# W5500_Module.net
KiCad netlist of a schematic drawn in Altium Designer
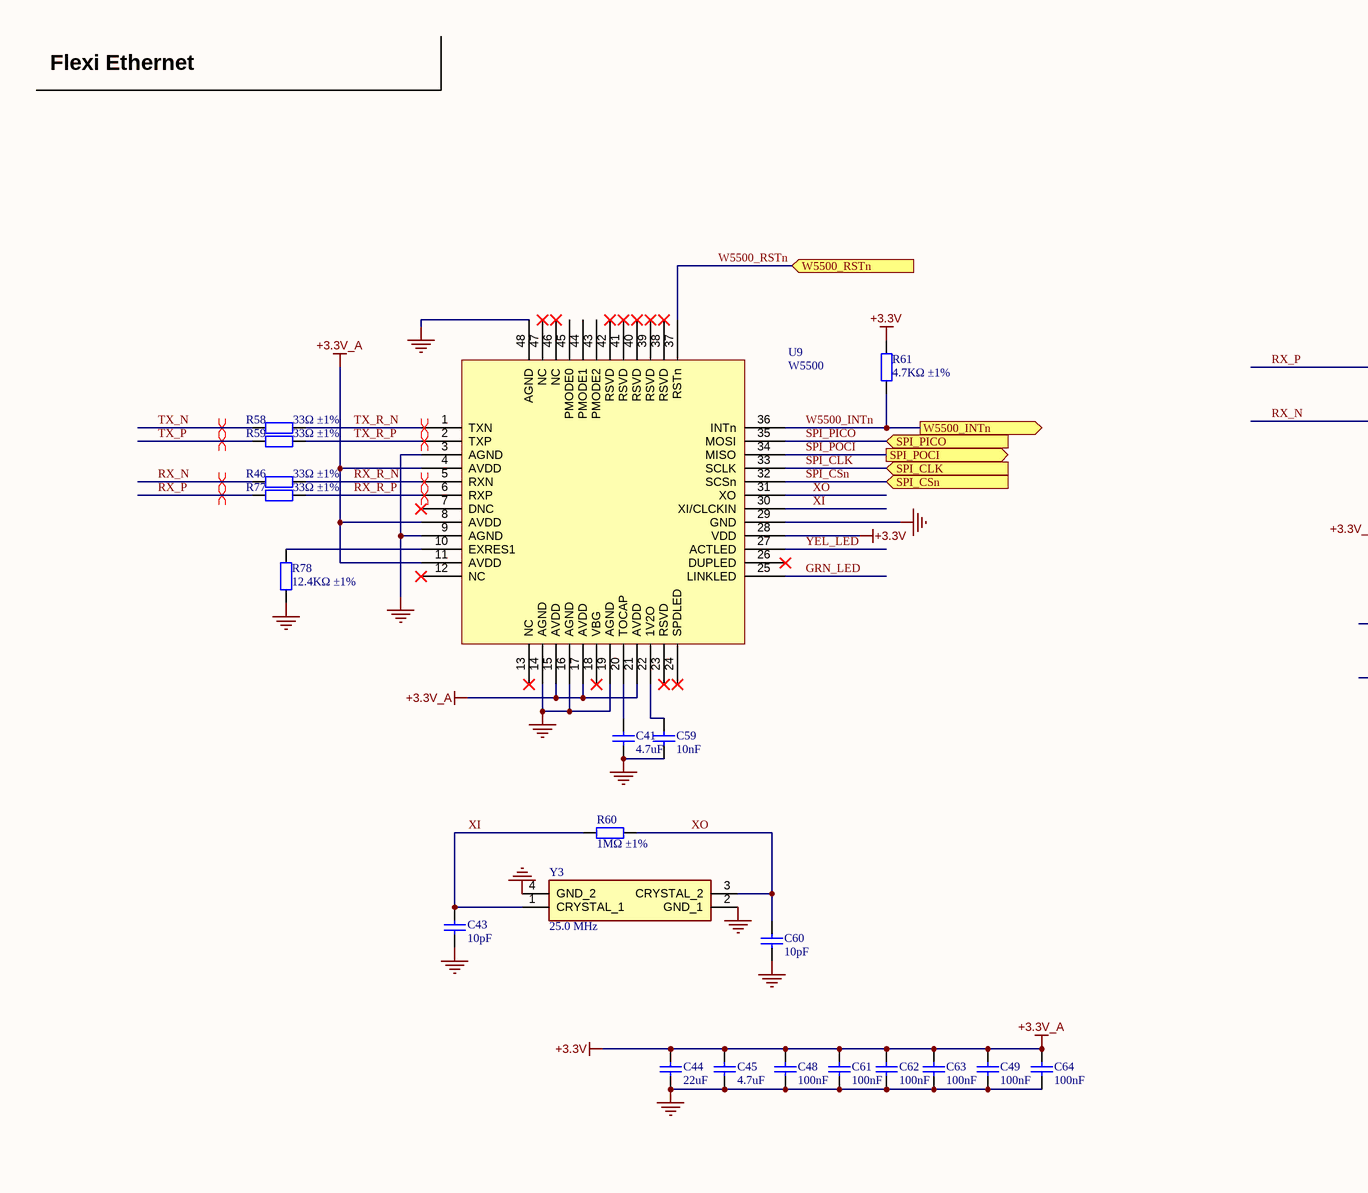
[diagram p0: W5500_Module.SchDoc, left]
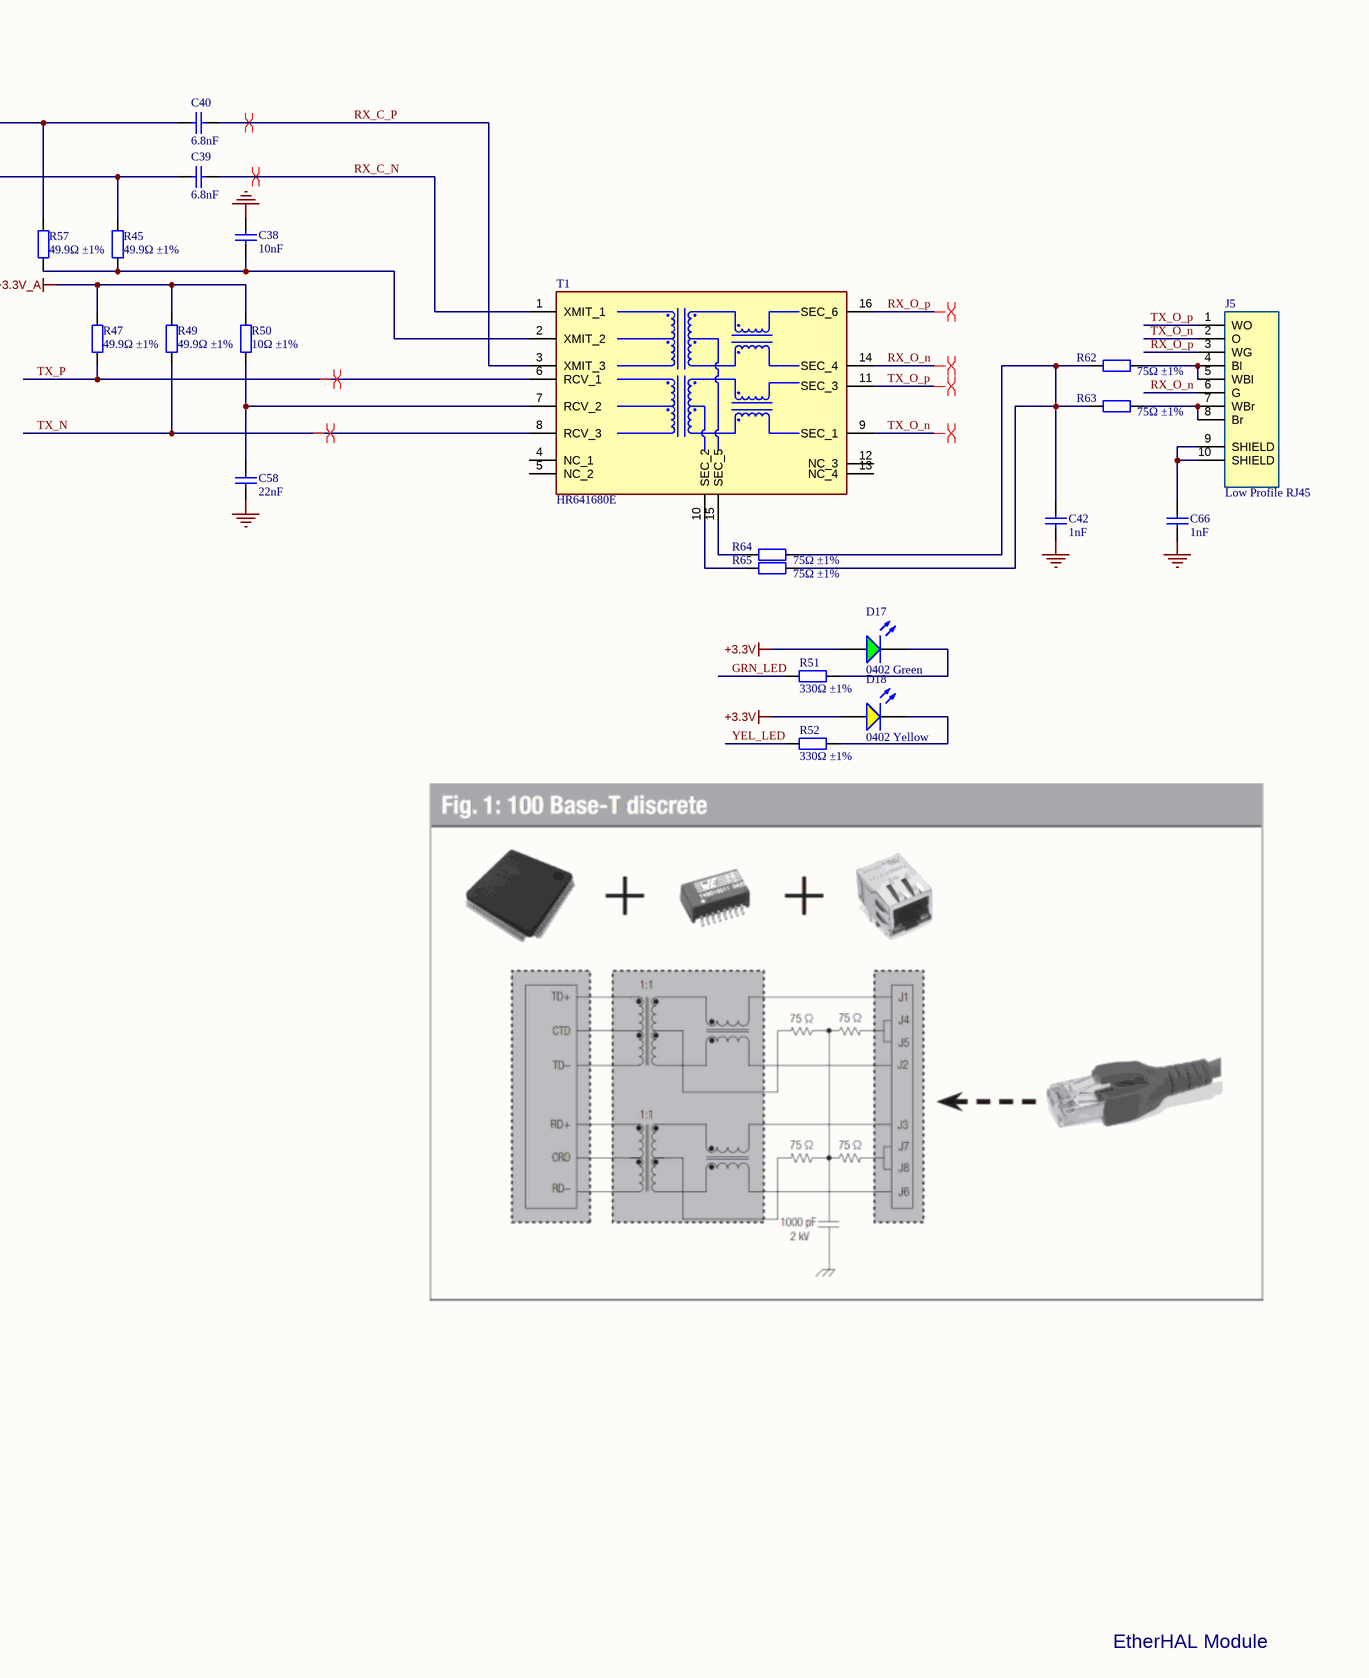
[diagram p1: W5500_Module.SchDoc, right]

(export (version "E")
  (design (tool "Eeschema 10.0.6"))
  (components
    (comp (ref "C38")
      (value "10nF")
      (footprint "0402_C")
      (description "Chip capacitors")
      (fields
        (field (name "MANUFACTURER") "Samsung Electro-Mechanics")
        (field (name "PARTNUMBER") "CL05B103KB5NNNC")
      )
      (libsource (lib "Cap") (part "0402 10nF (103) 10% 50V"))
    )
    (comp (ref "C39")
      (value "6.8nF")
      (footprint "0402_C")
      (description "Chip capacitors")
      (fields
        (field (name "MANUFACTURER") "Guangdong Fenghua Advanced Tech")
        (field (name "PARTNUMBER") "0402B682K500NT")
      )
      (libsource (lib "Cap") (part "0402 6.8nF (682) 10% 50V"))
    )
    (comp (ref "C40")
      (value "6.8nF")
      (footprint "0402_C")
      (description "Chip capacitors")
      (fields
        (field (name "MANUFACTURER") "Guangdong Fenghua Advanced Tech")
        (field (name "PARTNUMBER") "0402B682K500NT")
      )
      (libsource (lib "Cap") (part "0402 6.8nF (682) 10% 50V"))
    )
    (comp (ref "C41")
      (value "4.7uF")
      (footprint "0402_C")
      (description "Chip capacitor")
      (fields
        (field (name "MANUFACTURER") "Samsung Electro-Mechanics")
        (field (name "PARTNUMBER") "CL05A475MP5NRNC")
      )
      (libsource (lib "Cap") (part "0402 4.7uF (475) 20% 10V"))
    )
    (comp (ref "C42")
      (value "1nF")
      (footprint "1206_C")
      (description "Chip capacitors")
      (fields
        (field (name "MANUFACTURER") "Samsung Electro-Mechanics")
        (field (name "PARTNUMBER") "CL31B102KGFNNNE")
      )
      (libsource (lib "Cap") (part "1206 1nF (102) 10% 500V"))
    )
    (comp (ref "C43")
      (value "10pF")
      (footprint "0402_C")
      (description "Chip capacitors")
      (fields
        (field (name "MANUFACTURER") "Samsung Electro-Mechanics")
        (field (name "PARTNUMBER") "CL05C100JB5NNNC")
      )
      (libsource (lib "Cap") (part "0402 10pF (100) 5% 50V"))
    )
    (comp (ref "C44")
      (value "22uF")
      (footprint "0805_C")
      (description "Chip capacitors")
      (fields
        (field (name "MANUFACTURER") "Samsung Electro-Mechanics")
        (field (name "PARTNUMBER") "CL21A226MAQNNNE")
      )
      (libsource (lib "Cap") (part "0805 22uF (226) 20% 25V"))
    )
    (comp (ref "C45")
      (value "4.7uF")
      (footprint "0603_C")
      (description "Chip capacitors")
      (fields
        (field (name "MANUFACTURER") "Samsung Electro-Mechanics")
        (field (name "PARTNUMBER") "CL10A475KO8NNNC")
      )
      (libsource (lib "Cap") (part "0603 4.7uF (475) 10% 16V"))
    )
    (comp (ref "C48")
      (value "100nF")
      (footprint "0402_C")
      (description "Chip capacitors")
      (fields
        (field (name "MANUFACTURER") "Samsung Electro-Mechanics")
        (field (name "PARTNUMBER") "CL05B104KO5NNNC")
      )
      (libsource (lib "Cap") (part "0402 100nF (104) 10% 16V"))
    )
    (comp (ref "C49")
      (value "100nF")
      (footprint "0402_C")
      (description "Chip capacitors")
      (fields
        (field (name "MANUFACTURER") "Samsung Electro-Mechanics")
        (field (name "PARTNUMBER") "CL05B104KO5NNNC")
      )
      (libsource (lib "Cap") (part "0402 100nF (104) 10% 16V"))
    )
    (comp (ref "C58")
      (value "22nF")
      (footprint "0402_C")
      (description "Chip capacitors")
      (fields
        (field (name "MANUFACTURER") "Guangdong Fenghua Advanced Tech")
        (field (name "PARTNUMBER") "0402B223K500NT")
      )
      (libsource (lib "Cap") (part "0402 22nF (223) 10% 50V"))
    )
    (comp (ref "C59")
      (value "10nF")
      (footprint "0402_C")
      (description "Chip capacitors")
      (fields
        (field (name "MANUFACTURER") "Samsung Electro-Mechanics")
        (field (name "PARTNUMBER") "CL05B103KB5NNNC")
      )
      (libsource (lib "Cap") (part "0402 10nF (103) 10% 50V"))
    )
    (comp (ref "C60")
      (value "10pF")
      (footprint "0402_C")
      (description "Chip capacitors")
      (fields
        (field (name "MANUFACTURER") "Samsung Electro-Mechanics")
        (field (name "PARTNUMBER") "CL05C100JB5NNNC")
      )
      (libsource (lib "Cap") (part "0402 10pF (100) 5% 50V"))
    )
    (comp (ref "C61")
      (value "100nF")
      (footprint "0402_C")
      (description "Chip capacitors")
      (fields
        (field (name "MANUFACTURER") "Samsung Electro-Mechanics")
        (field (name "PARTNUMBER") "CL05B104KO5NNNC")
      )
      (libsource (lib "Cap") (part "0402 100nF (104) 10% 16V"))
    )
    (comp (ref "C62")
      (value "100nF")
      (footprint "0402_C")
      (description "Chip capacitors")
      (fields
        (field (name "MANUFACTURER") "Samsung Electro-Mechanics")
        (field (name "PARTNUMBER") "CL05B104KO5NNNC")
      )
      (libsource (lib "Cap") (part "0402 100nF (104) 10% 16V"))
    )
    (comp (ref "C63")
      (value "100nF")
      (footprint "0402_C")
      (description "Chip capacitors")
      (fields
        (field (name "MANUFACTURER") "Samsung Electro-Mechanics")
        (field (name "PARTNUMBER") "CL05B104KO5NNNC")
      )
      (libsource (lib "Cap") (part "0402 100nF (104) 10% 16V"))
    )
    (comp (ref "C64")
      (value "100nF")
      (footprint "0402_C")
      (description "Chip capacitors")
      (fields
        (field (name "MANUFACTURER") "Samsung Electro-Mechanics")
        (field (name "PARTNUMBER") "CL05B104KO5NNNC")
      )
      (libsource (lib "Cap") (part "0402 100nF (104) 10% 16V"))
    )
    (comp (ref "C66")
      (value "1nF")
      (footprint "1206_C")
      (description "Chip capacitors")
      (fields
        (field (name "MANUFACTURER") "Samsung Electro-Mechanics")
        (field (name "PARTNUMBER") "CL31B102KGFNNNE")
      )
      (libsource (lib "Cap") (part "1206 1nF (102) 10% 500V"))
    )
    (comp (ref "D17")
      (value "0402 Green")
      (footprint "LED 0402_1005 RED")
      (description "LED")
      (libsource (lib "LED") (part "0402 LED Green"))
    )
    (comp (ref "D18")
      (value "0402 Yellow")
      (footprint "LED 0402_1005 RED")
      (description "LED")
      (libsource (lib "LED") (part "0402 LED Yellow"))
    )
    (comp (ref "J5")
      (value "Low Profile RJ45")
      (footprint "RJ45-SMD_MJ88-B011-HLSV6-P")
      (description "Micro USB")
      (fields (field (name "MF") "Heling"))
      (libsource (lib "Universal_CNC_Breakout") (part "MJ88-B011-HLSV6-P"))
    )
    (comp (ref "R45")
      (value "49.9Ω ±1%")
      (footprint "0402_R")
      (description "Chip resistor")
      (fields (field (name "MANUFACTURER") "Uniroyal Elec") (field (name "PARTNUMBER") "0402WGF499JTCE"))
      (libsource (lib "RES") (part "0402 49.9R (49R9) 1%"))
    )
    (comp (ref "R46")
      (value "33Ω ±1%")
      (footprint "0402_R")
      (description "Chip resistor")
      (fields (field (name "MANUFACTURER") "Uniroyal Elec") (field (name "PARTNUMBER") "0402WGF330JTCE"))
      (libsource (lib "RES") (part "0402 33R (33R0) 1%"))
    )
    (comp (ref "R47")
      (value "49.9Ω ±1%")
      (footprint "0402_R")
      (description "Chip resistor")
      (fields (field (name "MANUFACTURER") "Uniroyal Elec") (field (name "PARTNUMBER") "0402WGF499JTCE"))
      (libsource (lib "") (part "0402 49.9R (49R9) 1%_1"))
    )
    (comp (ref "R49")
      (value "49.9Ω ±1%")
      (footprint "0402_R")
      (description "Chip resistor")
      (fields (field (name "MANUFACTURER") "Uniroyal Elec") (field (name "PARTNUMBER") "0402WGF499JTCE"))
      (libsource (lib "") (part "0402 49.9R (49R9) 1%_1"))
    )
    (comp (ref "R50")
      (value "10Ω ±1%")
      (footprint "0402_R")
      (description "Chip resistor")
      (fields (field (name "MANUFACTURER") "Uniroyal Elec") (field (name "PARTNUMBER") "0402WGF100JTCE"))
      (libsource (lib "RES") (part "0402 10R (10R0) 1%"))
    )
    (comp (ref "R51")
      (value "330Ω ±1%")
      (footprint "0402_R")
      (description "Chip resistor")
      (fields (field (name "MANUFACTURER") "Uniroyal Elec") (field (name "PARTNUMBER") "0402WGF3300TCE"))
      (libsource (lib "RES") (part "0402 330R (3300) 1%"))
    )
    (comp (ref "R52")
      (value "330Ω ±1%")
      (footprint "0402_R")
      (description "Chip resistor")
      (fields (field (name "MANUFACTURER") "Uniroyal Elec") (field (name "PARTNUMBER") "0402WGF3300TCE"))
      (libsource (lib "RES") (part "0402 330R (3300) 1%"))
    )
    (comp (ref "R57")
      (value "49.9Ω ±1%")
      (footprint "0402_R")
      (description "Chip resistor")
      (fields (field (name "MANUFACTURER") "Uniroyal Elec") (field (name "PARTNUMBER") "0402WGF499JTCE"))
      (libsource (lib "RES") (part "0402 49.9R (49R9) 1%"))
    )
    (comp (ref "R58")
      (value "33Ω ±1%")
      (footprint "0402_R")
      (description "Chip resistor")
      (fields (field (name "MANUFACTURER") "Uniroyal Elec") (field (name "PARTNUMBER") "0402WGF330JTCE"))
      (libsource (lib "RES") (part "0402 33R (33R0) 1%"))
    )
    (comp (ref "R59")
      (value "33Ω ±1%")
      (footprint "0402_R")
      (description "Chip resistor")
      (fields (field (name "MANUFACTURER") "Uniroyal Elec") (field (name "PARTNUMBER") "0402WGF330JTCE"))
      (libsource (lib "RES") (part "0402 33R (33R0) 1%"))
    )
    (comp (ref "R60")
      (value "1MΩ ±1%")
      (footprint "0402_R")
      (description "Chip resistor")
      (fields (field (name "MANUFACTURER") "Uniroyal Elec") (field (name "PARTNUMBER") "0402WGF1004TCE"))
      (libsource (lib "RES") (part "0402 1M (1004) 1%"))
    )
    (comp (ref "R61")
      (value "4.7KΩ ±1%")
      (footprint "0402_R")
      (description "Chip resistor")
      (fields (field (name "MANUFACTURER") "Uniroyal Elec") (field (name "PARTNUMBER") "0402WGF4701TCE"))
      (libsource (lib "RES") (part "0402 4.7K (4701) 1%"))
    )
    (comp (ref "R62")
      (value "75Ω ±1%")
      (footprint "0402_R")
      (description "Chip resistor")
      (fields (field (name "MANUFACTURER") "Uniroyal Elec") (field (name "PARTNUMBER") "0402WGF750JTCE"))
      (libsource (lib "RES") (part "0402 75R (75R0) 1%"))
    )
    (comp (ref "R63")
      (value "75Ω ±1%")
      (footprint "0402_R")
      (description "Chip resistor")
      (fields (field (name "MANUFACTURER") "Uniroyal Elec") (field (name "PARTNUMBER") "0402WGF750JTCE"))
      (libsource (lib "RES") (part "0402 75R (75R0) 1%"))
    )
    (comp (ref "R64")
      (value "75Ω ±1%")
      (footprint "0402_R")
      (description "Chip resistor")
      (fields (field (name "MANUFACTURER") "Uniroyal Elec") (field (name "PARTNUMBER") "0402WGF750JTCE"))
      (libsource (lib "RES") (part "0402 75R (75R0) 1%"))
    )
    (comp (ref "R65")
      (value "75Ω ±1%")
      (footprint "0402_R")
      (description "Chip resistor")
      (fields (field (name "MANUFACTURER") "Uniroyal Elec") (field (name "PARTNUMBER") "0402WGF750JTCE"))
      (libsource (lib "RES") (part "0402 75R (75R0) 1%"))
    )
    (comp (ref "R77")
      (value "33Ω ±1%")
      (footprint "0402_R")
      (description "Chip resistor")
      (fields (field (name "MANUFACTURER") "Uniroyal Elec") (field (name "PARTNUMBER") "0402WGF330JTCE"))
      (libsource (lib "RES") (part "0402 33R (33R0) 1%"))
    )
    (comp (ref "R78")
      (value "12.4KΩ ±1%")
      (footprint "0603_R")
      (description "Chip resistor")
      (fields (field (name "MANUFACTURER") "Uniroyal Elec") (field (name "PARTNUMBER") "0603WAF1242T5E"))
      (libsource (lib "RES") (part "0603 10K (1002) 1%"))
    )
    (comp (ref "T1")
      (value "HR641680E")
      (footprint "SamacSys:HR641680E")
      (description "Transformer")
      (libsource (lib "Universal_CNC_Breakout") (part "HR641680E"))
    )
    (comp (ref "U9")
      (value "W5500")
      (footprint "LQFP-48_7x7x05P")
      (description "Ethernet Controllers 2.97V ~ 3.63V 10/100 Base-T/TX PHY SPI LQFP-48_7x7x05P Ethernet ICs ROHS")
      (libsource (lib "IC") (part "W5500_[C32843]"))
    )
    (comp (ref "Y3")
      (value "25.0 MHz")
      (footprint "SamacSys:YSX321SL")
      (description "Crystal or Oscillator")
      (fields (field (name "MANUFACTURER_PART_NUMBER") "X322525MSB4SI"))
      (libsource (lib "*") (part "YSX321SL"))
    )
  )
  (nets
    (net (code "1") (name "+3.3V") (class "Default")
      (node (ref "C44") (pin "2") (pinfunction "2_2") (pintype "passive"))
      (node (ref "C45") (pin "2") (pinfunction "2_2") (pintype "passive"))
      (node (ref "C48") (pin "2") (pinfunction "2_2") (pintype "passive"))
      (node (ref "C49") (pin "2") (pinfunction "2_2") (pintype "passive"))
      (node (ref "C61") (pin "2") (pinfunction "2_2") (pintype "passive"))
      (node (ref "C62") (pin "2") (pinfunction "2_2") (pintype "passive"))
      (node (ref "C63") (pin "2") (pinfunction "2_2") (pintype "passive"))
      (node (ref "C64") (pin "2") (pinfunction "2_2") (pintype "passive"))
      (node (ref "D17") (pin "A") (pinfunction "A_A") (pintype "passive"))
      (node (ref "D18") (pin "A") (pinfunction "A_A") (pintype "passive"))
      (node (ref "R47") (pin "1") (pinfunction "1_1") (pintype "passive"))
      (node (ref "R49") (pin "1") (pinfunction "1_1") (pintype "passive"))
      (node (ref "R50") (pin "1") (pinfunction "1_1") (pintype "passive"))
      (node (ref "R61") (pin "1") (pinfunction "1_1") (pintype "passive"))
      (node (ref "U9") (pin "11") (pinfunction "AVDD_11") (pintype "passive"))
      (node (ref "U9") (pin "15") (pinfunction "AVDD_15") (pintype "passive"))
      (node (ref "U9") (pin "17") (pinfunction "AVDD_17") (pintype "passive"))
      (node (ref "U9") (pin "21") (pinfunction "AVDD_21") (pintype "passive"))
      (node (ref "U9") (pin "28") (pinfunction "VDD_28") (pintype "passive"))
      (node (ref "U9") (pin "4") (pinfunction "AVDD_4") (pintype "passive"))
      (node (ref "U9") (pin "8") (pinfunction "AVDD_8") (pintype "passive"))
    )
    (net (code "2") (name "/GRN_LED") (class "Default")
      (node (ref "R51") (pin "1") (pinfunction "1_1") (pintype "passive"))
      (node (ref "U9") (pin "25") (pinfunction "LINKLED_25") (pintype "passive"))
    )
    (net (code "3") (name "/RX_C_N") (class "Default")
      (node (ref "C39") (pin "1") (pinfunction "1_1") (pintype "passive"))
      (node (ref "T1") (pin "1") (pinfunction "XMIT_1_1") (pintype "passive"))
    )
    (net (code "4") (name "/RX_C_P") (class "Default")
      (node (ref "C40") (pin "1") (pinfunction "1_1") (pintype "passive"))
      (node (ref "T1") (pin "3") (pinfunction "XMIT_3_3") (pintype "passive"))
    )
    (net (code "5") (name "/RX_N") (class "Default")
      (node (ref "C39") (pin "2") (pinfunction "2_2") (pintype "passive"))
      (node (ref "R45") (pin "2") (pinfunction "2_2") (pintype "passive"))
      (node (ref "R46") (pin "1") (pinfunction "1_1") (pintype "passive"))
    )
    (net (code "6") (name "/RX_O_n") (class "Default")
      (node (ref "J5") (pin "6") (pinfunction "G_6") (pintype "passive"))
      (node (ref "T1") (pin "14") (pinfunction "SEC_4_14") (pintype "passive"))
    )
    (net (code "7") (name "/RX_O_p") (class "Default")
      (node (ref "J5") (pin "3") (pinfunction "WG_3") (pintype "passive"))
      (node (ref "T1") (pin "16") (pinfunction "SEC_6_16") (pintype "passive"))
    )
    (net (code "8") (name "/RX_P") (class "Default")
      (node (ref "C40") (pin "2") (pinfunction "2_2") (pintype "passive"))
      (node (ref "R57") (pin "2") (pinfunction "2_2") (pintype "passive"))
      (node (ref "R77") (pin "1") (pinfunction "1_1") (pintype "passive"))
    )
    (net (code "9") (name "/RX_R_N") (class "Default")
      (node (ref "R46") (pin "2") (pinfunction "2_2") (pintype "passive"))
      (node (ref "U9") (pin "5") (pinfunction "RXN_5") (pintype "passive"))
    )
    (net (code "10") (name "/RX_R_P") (class "Default")
      (node (ref "R77") (pin "2") (pinfunction "2_2") (pintype "passive"))
      (node (ref "U9") (pin "6") (pinfunction "RXP_6") (pintype "passive"))
    )
    (net (code "11") (name "/SPI_CLK") (class "Default")
      (node (ref "U9") (pin "33") (pinfunction "SCLK_33") (pintype "passive"))
    )
    (net (code "12") (name "/SPI_CSn") (class "Default")
      (node (ref "U9") (pin "32") (pinfunction "SCSn_32") (pintype "passive"))
    )
    (net (code "13") (name "/SPI_PICO") (class "Default")
      (node (ref "U9") (pin "35") (pinfunction "MOSI_35") (pintype "passive"))
    )
    (net (code "14") (name "/SPI_POCI") (class "Default")
      (node (ref "U9") (pin "34") (pinfunction "MISO_34") (pintype "passive"))
    )
    (net (code "15") (name "/TX_N") (class "Default")
      (node (ref "R49") (pin "2") (pinfunction "2_2") (pintype "passive"))
      (node (ref "R58") (pin "1") (pinfunction "1_1") (pintype "passive"))
      (node (ref "T1") (pin "8") (pinfunction "RCV_3_8") (pintype "passive"))
    )
    (net (code "16") (name "/TX_O_n") (class "Default")
      (node (ref "J5") (pin "2") (pinfunction "O_2") (pintype "passive"))
      (node (ref "T1") (pin "9") (pinfunction "SEC_1_9") (pintype "passive"))
    )
    (net (code "17") (name "/TX_O_p") (class "Default")
      (node (ref "J5") (pin "1") (pinfunction "WO_1") (pintype "power_in"))
      (node (ref "T1") (pin "11") (pinfunction "SEC_3_11") (pintype "passive"))
    )
    (net (code "18") (name "/TX_P") (class "Default")
      (node (ref "R47") (pin "2") (pinfunction "2_2") (pintype "passive"))
      (node (ref "R59") (pin "1") (pinfunction "1_1") (pintype "passive"))
      (node (ref "T1") (pin "6") (pinfunction "RCV_1_6") (pintype "passive"))
    )
    (net (code "19") (name "/TX_R_N") (class "Default")
      (node (ref "R58") (pin "2") (pinfunction "2_2") (pintype "passive"))
      (node (ref "U9") (pin "1") (pinfunction "TXN_1") (pintype "passive"))
    )
    (net (code "20") (name "/TX_R_P") (class "Default")
      (node (ref "R59") (pin "2") (pinfunction "2_2") (pintype "passive"))
      (node (ref "U9") (pin "2") (pinfunction "TXP_2") (pintype "passive"))
    )
    (net (code "21") (name "/W5500_INTn") (class "Default")
      (node (ref "R61") (pin "2") (pinfunction "2_2") (pintype "passive"))
      (node (ref "U9") (pin "36") (pinfunction "INTn_36") (pintype "passive"))
    )
    (net (code "22") (name "/W5500_RSTn") (class "Default")
      (node (ref "U9") (pin "37") (pinfunction "RSTn_37") (pintype "passive"))
    )
    (net (code "23") (name "/XI") (class "Default")
      (node (ref "C43") (pin "2") (pinfunction "2_2") (pintype "passive"))
      (node (ref "R60") (pin "1") (pinfunction "1_1") (pintype "passive"))
      (node (ref "U9") (pin "30") (pinfunction "XI/CLCKIN_30") (pintype "passive"))
      (node (ref "Y3") (pin "1") (pinfunction "CRYSTAL_1_1") (pintype "passive"))
    )
    (net (code "24") (name "/XO") (class "Default")
      (node (ref "C60") (pin "2") (pinfunction "2_2") (pintype "passive"))
      (node (ref "R60") (pin "2") (pinfunction "2_2") (pintype "passive"))
      (node (ref "U9") (pin "31") (pinfunction "XO_31") (pintype "passive"))
      (node (ref "Y3") (pin "3") (pinfunction "CRYSTAL_2_3") (pintype "passive"))
    )
    (net (code "25") (name "/YEL_LED") (class "Default")
      (node (ref "R52") (pin "1") (pinfunction "1_1") (pintype "passive"))
      (node (ref "U9") (pin "27") (pinfunction "ACTLED_27") (pintype "passive"))
    )
    (net (code "26") (name "GND") (class "Default")
      (node (ref "C38") (pin "1") (pinfunction "1_1") (pintype "passive"))
      (node (ref "C41") (pin "1") (pinfunction "1_1") (pintype "passive"))
      (node (ref "C42") (pin "1") (pinfunction "1_1") (pintype "passive"))
      (node (ref "C43") (pin "1") (pinfunction "1_1") (pintype "passive"))
      (node (ref "C44") (pin "1") (pinfunction "1_1") (pintype "passive"))
      (node (ref "C45") (pin "1") (pinfunction "1_1") (pintype "passive"))
      (node (ref "C48") (pin "1") (pinfunction "1_1") (pintype "passive"))
      (node (ref "C49") (pin "1") (pinfunction "1_1") (pintype "passive"))
      (node (ref "C58") (pin "1") (pinfunction "1_1") (pintype "passive"))
      (node (ref "C59") (pin "1") (pinfunction "1_1") (pintype "passive"))
      (node (ref "C60") (pin "1") (pinfunction "1_1") (pintype "passive"))
      (node (ref "C61") (pin "1") (pinfunction "1_1") (pintype "passive"))
      (node (ref "C62") (pin "1") (pinfunction "1_1") (pintype "passive"))
      (node (ref "C63") (pin "1") (pinfunction "1_1") (pintype "passive"))
      (node (ref "C64") (pin "1") (pinfunction "1_1") (pintype "passive"))
      (node (ref "C66") (pin "1") (pinfunction "1_1") (pintype "passive"))
      (node (ref "R78") (pin "1") (pinfunction "1_1") (pintype "passive"))
      (node (ref "U9") (pin "14") (pinfunction "AGND_14") (pintype "passive"))
      (node (ref "U9") (pin "16") (pinfunction "AGND_16") (pintype "passive"))
      (node (ref "U9") (pin "19") (pinfunction "AGND_19") (pintype "passive"))
      (node (ref "U9") (pin "29") (pinfunction "GND_29") (pintype "passive"))
      (node (ref "U9") (pin "3") (pinfunction "AGND_3") (pintype "passive"))
      (node (ref "U9") (pin "48") (pinfunction "AGND_48") (pintype "passive"))
      (node (ref "U9") (pin "9") (pinfunction "AGND_9") (pintype "passive"))
      (node (ref "Y3") (pin "2") (pinfunction "GND_1_2") (pintype "passive"))
      (node (ref "Y3") (pin "4") (pinfunction "GND_2_4") (pintype "passive"))
    )
    (net (code "27") (name "Net-(C42-Pad2)") (class "Default")
      (node (ref "C42") (pin "2") (pinfunction "2_2") (pintype "passive"))
      (node (ref "R62") (pin "2") (pinfunction "2_2") (pintype "passive"))
      (node (ref "R63") (pin "2") (pinfunction "2_2") (pintype "passive"))
      (node (ref "R64") (pin "1") (pinfunction "1_1") (pintype "passive"))
      (node (ref "R65") (pin "1") (pinfunction "1_1") (pintype "passive"))
    )
    (net (code "28") (name "Net-(C66-Pad2)") (class "Default")
      (node (ref "C66") (pin "2") (pinfunction "2_2") (pintype "passive"))
      (node (ref "J5") (pin "10") (pinfunction "SHIELD_10") (pintype "passive"))
      (node (ref "J5") (pin "9") (pinfunction "SHIELD_9") (pintype "passive"))
    )
    (net (code "29") (name "Net-(D17-PadK)") (class "Default")
      (node (ref "D17") (pin "K") (pinfunction "K_K") (pintype "passive"))
      (node (ref "R51") (pin "2") (pinfunction "2_2") (pintype "passive"))
    )
    (net (code "30") (name "Net-(D18-PadK)") (class "Default")
      (node (ref "D18") (pin "K") (pinfunction "K_K") (pintype "passive"))
      (node (ref "R52") (pin "2") (pinfunction "2_2") (pintype "passive"))
    )
    (net (code "31") (name "Net-(J5-Bl)") (class "Default")
      (node (ref "J5") (pin "4") (pinfunction "Bl_4") (pintype "passive"))
      (node (ref "J5") (pin "5") (pinfunction "WBl_5") (pintype "power_in"))
      (node (ref "R62") (pin "1") (pinfunction "1_1") (pintype "passive"))
    )
    (net (code "32") (name "Net-(J5-Br)") (class "Default")
      (node (ref "J5") (pin "7") (pinfunction "WBr_7") (pintype "passive"))
      (node (ref "J5") (pin "8") (pinfunction "Br_8") (pintype "passive"))
      (node (ref "R63") (pin "1") (pinfunction "1_1") (pintype "passive"))
    )
    (net (code "33") (name "Net-(T1-RCV_2)") (class "Default")
      (node (ref "C58") (pin "2") (pinfunction "2_2") (pintype "passive"))
      (node (ref "R50") (pin "2") (pinfunction "2_2") (pintype "passive"))
      (node (ref "T1") (pin "7") (pinfunction "RCV_2_7") (pintype "passive"))
    )
    (net (code "34") (name "Net-(T1-SEC_2)") (class "Default")
      (node (ref "R65") (pin "2") (pinfunction "2_2") (pintype "passive"))
      (node (ref "T1") (pin "10") (pinfunction "SEC_2_10") (pintype "passive"))
    )
    (net (code "35") (name "Net-(T1-SEC_5)") (class "Default")
      (node (ref "R64") (pin "2") (pinfunction "2_2") (pintype "passive"))
      (node (ref "T1") (pin "15") (pinfunction "SEC_5_15") (pintype "passive"))
    )
    (net (code "36") (name "Net-(T1-XMIT_2)") (class "Default")
      (node (ref "C38") (pin "2") (pinfunction "2_2") (pintype "passive"))
      (node (ref "R45") (pin "1") (pinfunction "1_1") (pintype "passive"))
      (node (ref "R57") (pin "1") (pinfunction "1_1") (pintype "passive"))
      (node (ref "T1") (pin "2") (pinfunction "XMIT_2_2") (pintype "passive"))
    )
    (net (code "37") (name "Net-(U9-1V2O)") (class "Default")
      (node (ref "C59") (pin "2") (pinfunction "2_2") (pintype "passive"))
      (node (ref "U9") (pin "22") (pinfunction "1V2O_22") (pintype "passive"))
    )
    (net (code "38") (name "Net-(U9-EXRES1)") (class "Default")
      (node (ref "R78") (pin "2") (pinfunction "2_2") (pintype "passive"))
      (node (ref "U9") (pin "10") (pinfunction "EXRES1_10") (pintype "passive"))
    )
    (net (code "39") (name "Net-(U9-TOCAP)") (class "Default")
      (node (ref "C41") (pin "2") (pinfunction "2_2") (pintype "passive"))
      (node (ref "U9") (pin "20") (pinfunction "TOCAP_20") (pintype "passive"))
    )
    (net (code "40") (name "unconnected-(T1-NC_1-Pad4)") (class "Default")
      (node (ref "T1") (pin "4") (pinfunction "NC_1_4") (pintype "passive"))
    )
    (net (code "41") (name "unconnected-(T1-NC_2-Pad5)") (class "Default")
      (node (ref "T1") (pin "5") (pinfunction "NC_2_5") (pintype "passive"))
    )
    (net (code "42") (name "unconnected-(T1-NC_3-Pad12)") (class "Default")
      (node (ref "T1") (pin "12") (pinfunction "NC_3_12") (pintype "passive"))
    )
    (net (code "43") (name "unconnected-(T1-NC_4-Pad13)") (class "Default")
      (node (ref "T1") (pin "13") (pinfunction "NC_4_13") (pintype "passive"))
    )
    (net (code "44") (name "unconnected-(U9-DNC-Pad7)") (class "Default")
      (node (ref "U9") (pin "7") (pinfunction "DNC_7") (pintype "passive+no_connect"))
    )
    (net (code "45") (name "unconnected-(U9-DUPLED-Pad26)") (class "Default")
      (node (ref "U9") (pin "26") (pinfunction "DUPLED_26") (pintype "passive+no_connect"))
    )
    (net (code "46") (name "unconnected-(U9-NC-Pad12)") (class "Default")
      (node (ref "U9") (pin "12") (pinfunction "NC_12") (pintype "passive+no_connect"))
    )
    (net (code "47") (name "unconnected-(U9-NC-Pad13)") (class "Default")
      (node (ref "U9") (pin "13") (pinfunction "NC_13") (pintype "passive+no_connect"))
    )
    (net (code "48") (name "unconnected-(U9-NC-Pad46)") (class "Default")
      (node (ref "U9") (pin "46") (pinfunction "NC_46") (pintype "passive+no_connect"))
    )
    (net (code "49") (name "unconnected-(U9-NC-Pad47)") (class "Default")
      (node (ref "U9") (pin "47") (pinfunction "NC_47") (pintype "passive+no_connect"))
    )
    (net (code "50") (name "unconnected-(U9-PMODE0-Pad45)") (class "Default")
      (node (ref "U9") (pin "45") (pinfunction "PMODE0_45") (pintype "passive"))
    )
    (net (code "51") (name "unconnected-(U9-PMODE1-Pad44)") (class "Default")
      (node (ref "U9") (pin "44") (pinfunction "PMODE1_44") (pintype "passive"))
    )
    (net (code "52") (name "unconnected-(U9-PMODE2-Pad43)") (class "Default")
      (node (ref "U9") (pin "43") (pinfunction "PMODE2_43") (pintype "passive"))
    )
    (net (code "53") (name "unconnected-(U9-RSVD-Pad23)") (class "Default")
      (node (ref "U9") (pin "23") (pinfunction "RSVD_23") (pintype "passive+no_connect"))
    )
    (net (code "54") (name "unconnected-(U9-RSVD-Pad38)") (class "Default")
      (node (ref "U9") (pin "38") (pinfunction "RSVD_38") (pintype "passive+no_connect"))
    )
    (net (code "55") (name "unconnected-(U9-RSVD-Pad39)") (class "Default")
      (node (ref "U9") (pin "39") (pinfunction "RSVD_39") (pintype "passive+no_connect"))
    )
    (net (code "56") (name "unconnected-(U9-RSVD-Pad40)") (class "Default")
      (node (ref "U9") (pin "40") (pinfunction "RSVD_40") (pintype "passive+no_connect"))
    )
    (net (code "57") (name "unconnected-(U9-RSVD-Pad41)") (class "Default")
      (node (ref "U9") (pin "41") (pinfunction "RSVD_41") (pintype "passive+no_connect"))
    )
    (net (code "58") (name "unconnected-(U9-RSVD-Pad42)") (class "Default")
      (node (ref "U9") (pin "42") (pinfunction "RSVD_42") (pintype "passive+no_connect"))
    )
    (net (code "59") (name "unconnected-(U9-SPDLED-Pad24)") (class "Default")
      (node (ref "U9") (pin "24") (pinfunction "SPDLED_24") (pintype "passive+no_connect"))
    )
    (net (code "60") (name "unconnected-(U9-VBG-Pad18)") (class "Default")
      (node (ref "U9") (pin "18") (pinfunction "VBG_18") (pintype "passive+no_connect"))
    )
  )
)
